# LDAQ-BASE.net
KiCad netlist of a schematic drawn in EAGLE
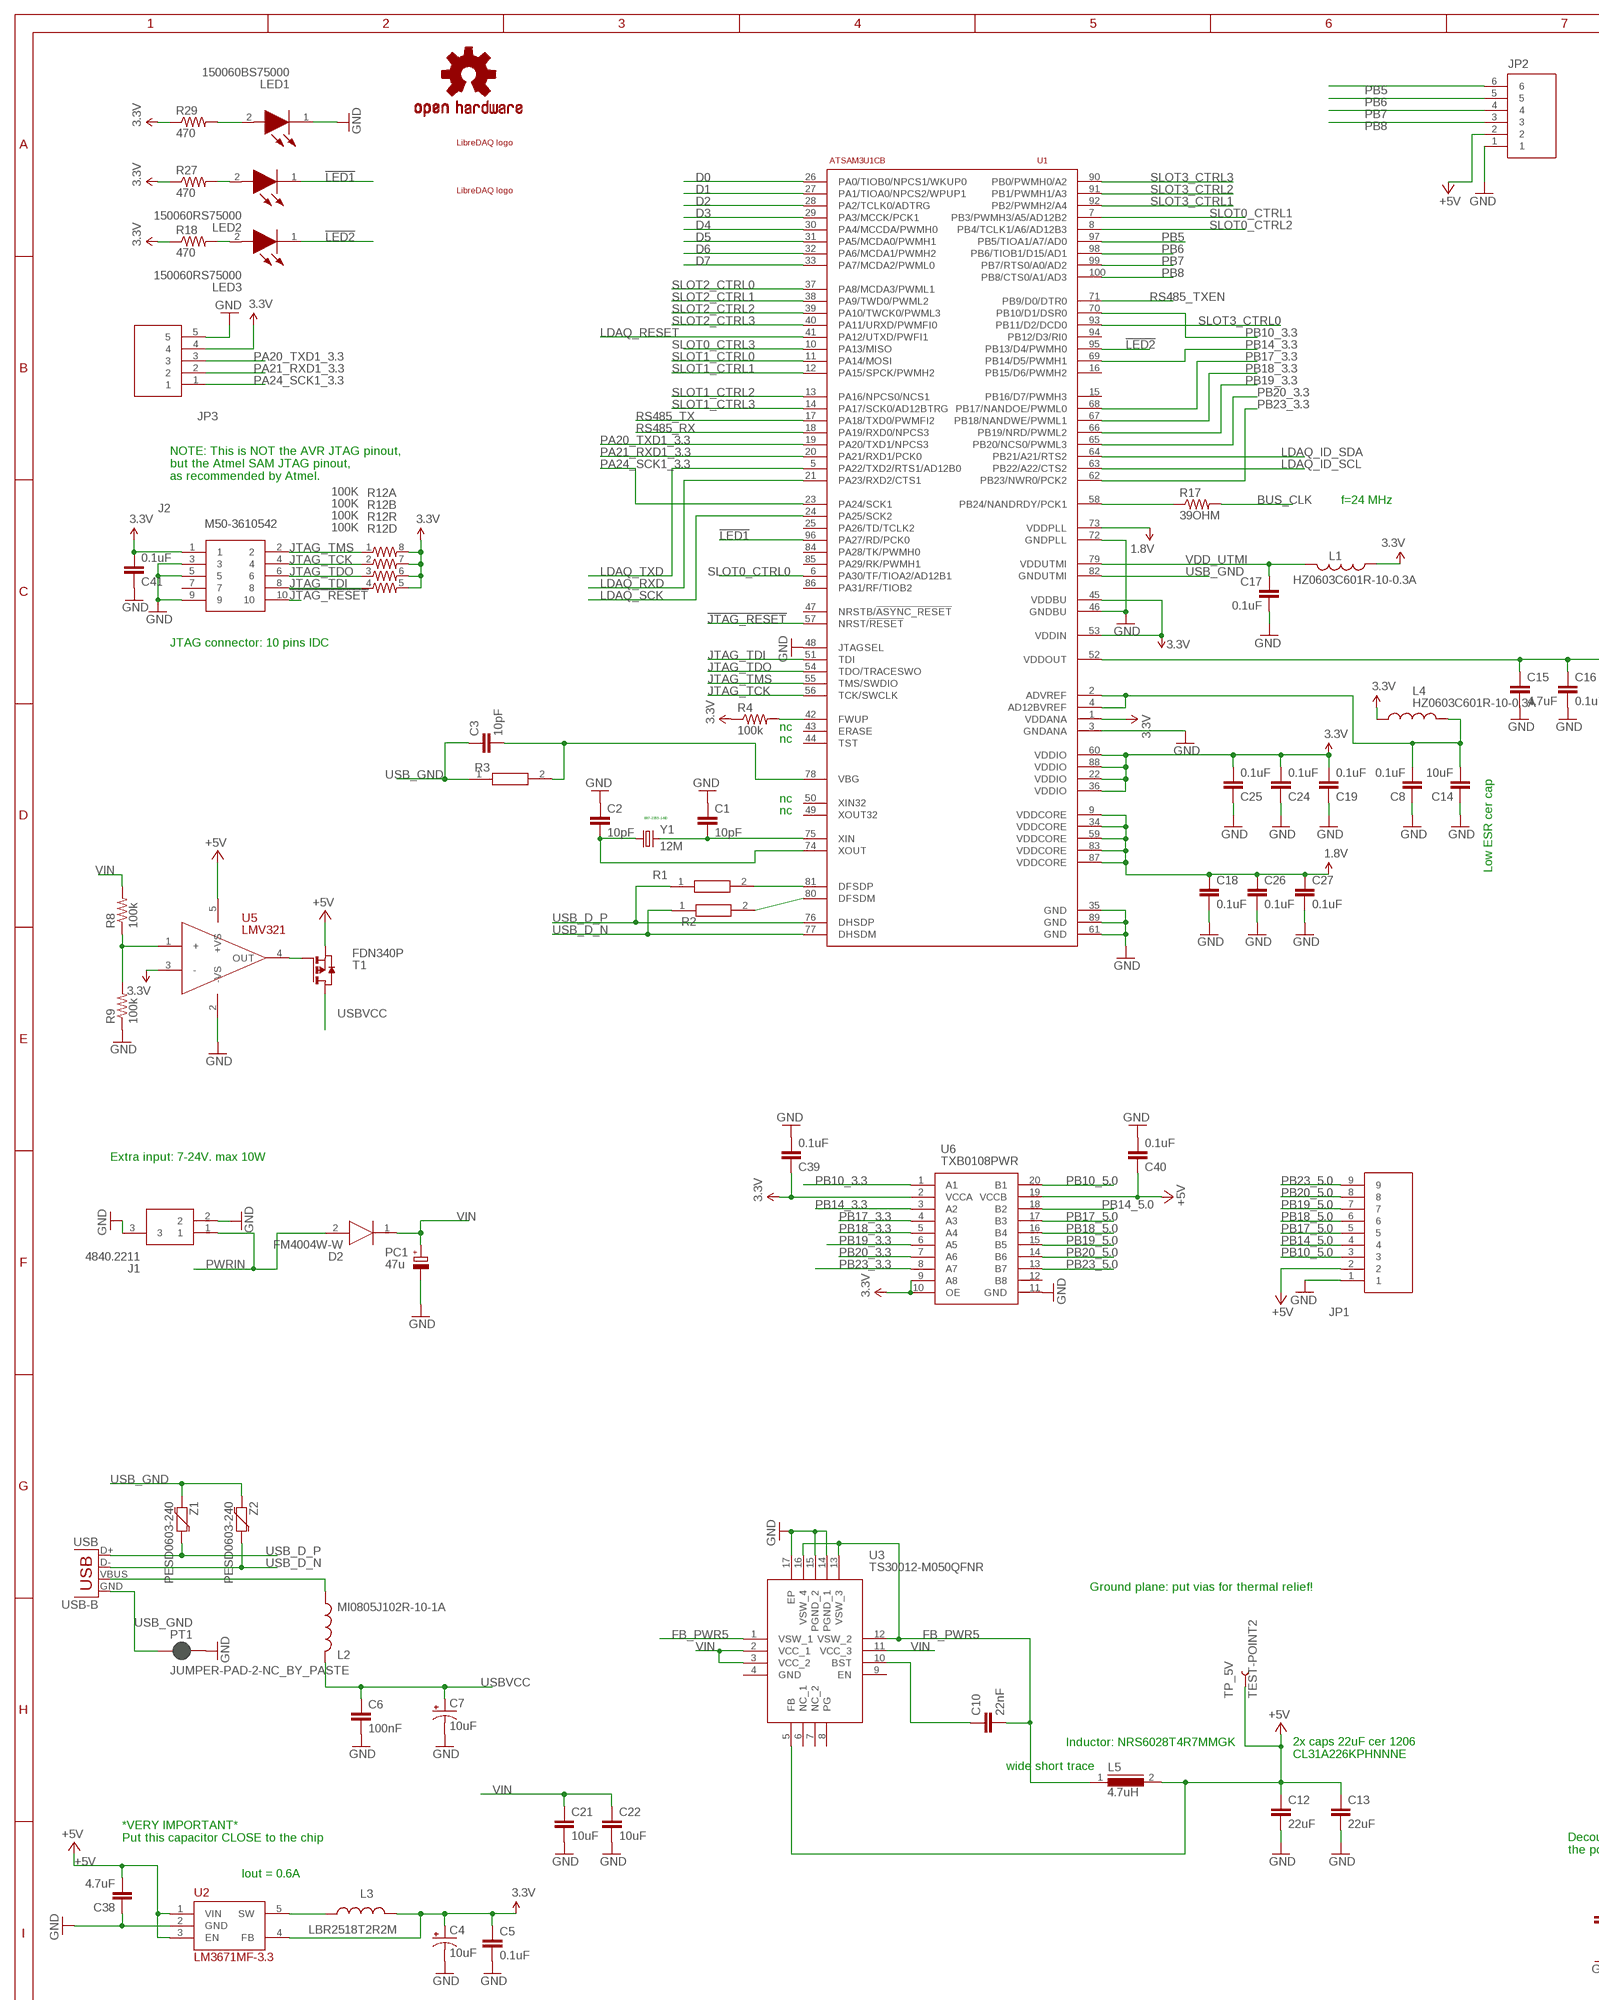
[diagram p0: schematic, sheet 1, part 1 of 2]
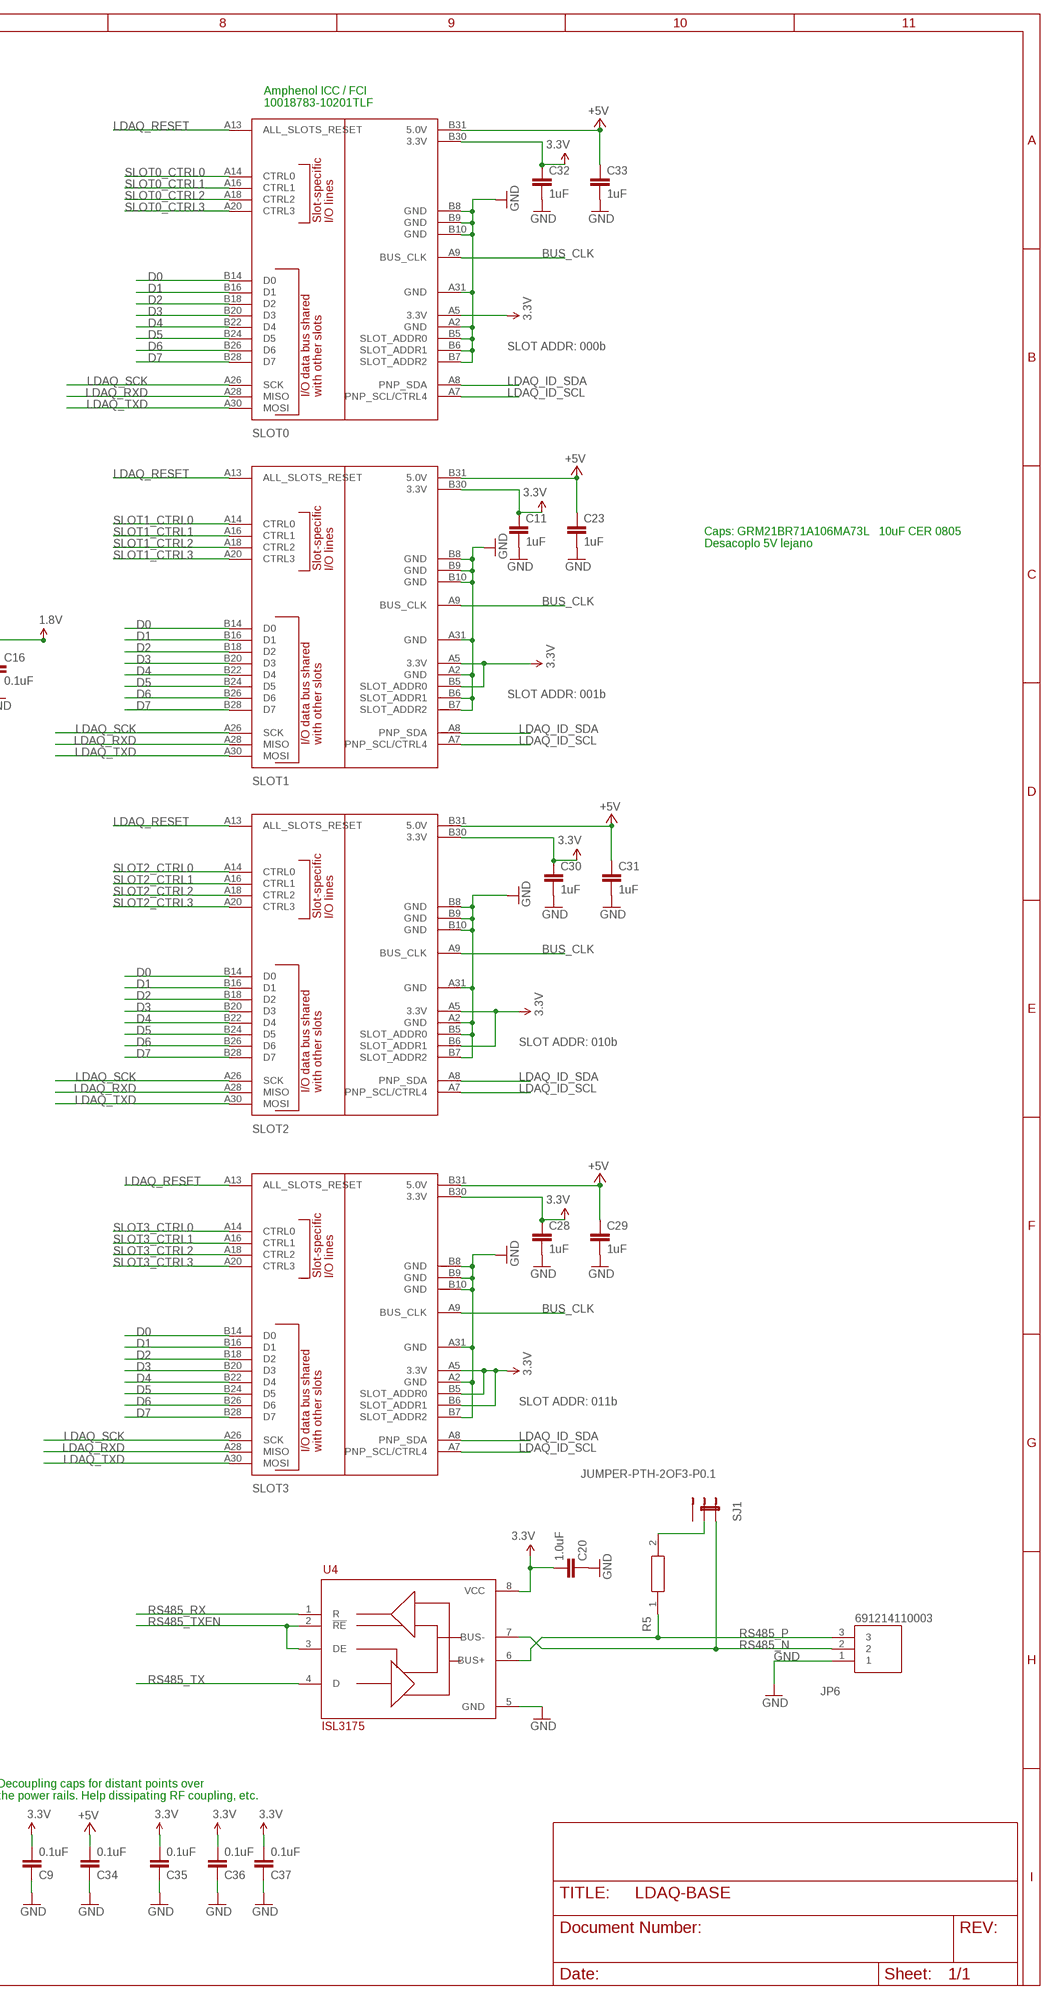
[diagram p1: schematic, sheet 1, part 2 of 2]

(export (version "E")
  (design (tool "Eeschema 10.0.6"))
  (components
    (comp (ref "C1")
      (value "10pF")
      (footprint "eagle-import:0603-CAP")
      (libsource (lib "eagle-import") (part "22PF-50V-5%(0603)"))
    )
    (comp (ref "C2")
      (value "10pF")
      (footprint "eagle-import:0603-CAP")
      (libsource (lib "eagle-import") (part "22PF-50V-5%(0603)"))
    )
    (comp (ref "C3")
      (value "10pF")
      (footprint "eagle-import:0603-CAP")
      (libsource (lib "eagle-import") (part "10PF-50V-5%(0603)"))
    )
    (comp (ref "C4")
      (value "10uF")
      (footprint "eagle-import:EIA3216")
      (libsource (lib "eagle-import") (part "10UF-16V-10%(TANT)"))
    )
    (comp (ref "C5")
      (value "0.1uF")
      (footprint "eagle-import:0603-CAP")
      (libsource (lib "eagle-import") (part "0.1UF-25V(+80/-20%)(0603)"))
    )
    (comp (ref "C6")
      (value "100nF")
      (footprint "eagle-import:0603-CAP")
      (libsource (lib "eagle-import") (part "CAP0603-CAP"))
    )
    (comp (ref "C7")
      (value "10uF")
      (footprint "eagle-import:EIA3216")
      (libsource (lib "eagle-import") (part "CAP_POL1206"))
    )
    (comp (ref "C8")
      (value "0.1uF")
      (footprint "eagle-import:0603-CAP")
      (libsource (lib "eagle-import") (part "0.1UF-25V(+80/-20%)(0603)"))
    )
    (comp (ref "C9")
      (value "0.1uF")
      (footprint "eagle-import:0603-CAP")
      (libsource (lib "eagle-import") (part "0.1UF-25V(+80/-20%)(0603)"))
    )
    (comp (ref "C10")
      (value "22nF")
      (footprint "eagle-import:0603-CAP")
      (libsource (lib "eagle-import") (part "0.1UF-25V(+80/-20%)(0603)"))
    )
    (comp (ref "C11")
      (value "1uF")
      (footprint "eagle-import:0805")
      (libsource (lib "eagle-import") (part "CAP-0805"))
    )
    (comp (ref "C12")
      (value "22uF")
      (footprint "eagle-import:1206")
      (libsource (lib "eagle-import") (part "CAP-1206"))
    )
    (comp (ref "C13")
      (value "22uF")
      (footprint "eagle-import:1206")
      (libsource (lib "eagle-import") (part "CAP-1206"))
    )
    (comp (ref "C14")
      (value "10uF")
      (footprint "eagle-import:0603-CAP")
      (libsource (lib "eagle-import") (part "10UF-6.3V-20%(0603)"))
    )
    (comp (ref "C15")
      (value "4.7uF")
      (footprint "eagle-import:0603-CAP")
      (libsource (lib "eagle-import") (part "4.7UF-6.3V-10%(0603)0603"))
    )
    (comp (ref "C16")
      (value "0.1uF")
      (footprint "eagle-import:0603-CAP")
      (libsource (lib "eagle-import") (part "0.1UF-25V(+80/-20%)(0603)"))
    )
    (comp (ref "C17")
      (value "0.1uF")
      (footprint "eagle-import:0603-CAP")
      (libsource (lib "eagle-import") (part "0.1UF-25V(+80/-20%)(0603)"))
    )
    (comp (ref "C18")
      (value "0.1uF")
      (footprint "eagle-import:0603-CAP")
      (libsource (lib "eagle-import") (part "0.1UF-25V(+80/-20%)(0603)"))
    )
    (comp (ref "C19")
      (value "0.1uF")
      (footprint "eagle-import:0603-CAP")
      (libsource (lib "eagle-import") (part "0.1UF-25V(+80/-20%)(0603)"))
    )
    (comp (ref "C20")
      (value "1.0uF")
      (footprint "eagle-import:0603-CAP")
      (libsource (lib "eagle-import") (part "1.0UF-16V-10%(0603)"))
    )
    (comp (ref "C21")
      (value "10uF")
      (footprint "eagle-import:1206")
      (libsource (lib "eagle-import") (part "CAP-1206"))
    )
    (comp (ref "C22")
      (value "10uF")
      (footprint "eagle-import:1206")
      (libsource (lib "eagle-import") (part "CAP-1206"))
    )
    (comp (ref "C23")
      (value "1uF")
      (footprint "eagle-import:0805")
      (libsource (lib "eagle-import") (part "CAP-0805"))
    )
    (comp (ref "C24")
      (value "0.1uF")
      (footprint "eagle-import:0603-CAP")
      (libsource (lib "eagle-import") (part "0.1UF-25V(+80/-20%)(0603)"))
    )
    (comp (ref "C25")
      (value "0.1uF")
      (footprint "eagle-import:0603-CAP")
      (libsource (lib "eagle-import") (part "0.1UF-25V(+80/-20%)(0603)"))
    )
    (comp (ref "C26")
      (value "0.1uF")
      (footprint "eagle-import:0603-CAP")
      (libsource (lib "eagle-import") (part "0.1UF-25V(+80/-20%)(0603)"))
    )
    (comp (ref "C27")
      (value "0.1uF")
      (footprint "eagle-import:0603-CAP")
      (libsource (lib "eagle-import") (part "0.1UF-25V(+80/-20%)(0603)"))
    )
    (comp (ref "C28")
      (value "1uF")
      (footprint "eagle-import:0805")
      (libsource (lib "eagle-import") (part "CAP-0805"))
    )
    (comp (ref "C29")
      (value "1uF")
      (footprint "eagle-import:0805")
      (libsource (lib "eagle-import") (part "CAP-0805"))
    )
    (comp (ref "C30")
      (value "1uF")
      (footprint "eagle-import:0805")
      (libsource (lib "eagle-import") (part "CAP-0805"))
    )
    (comp (ref "C31")
      (value "1uF")
      (footprint "eagle-import:0805")
      (libsource (lib "eagle-import") (part "CAP-0805"))
    )
    (comp (ref "C32")
      (value "1uF")
      (footprint "eagle-import:0805")
      (libsource (lib "eagle-import") (part "CAP-0805"))
    )
    (comp (ref "C33")
      (value "1uF")
      (footprint "eagle-import:0805")
      (libsource (lib "eagle-import") (part "CAP-0805"))
    )
    (comp (ref "C34")
      (value "0.1uF")
      (footprint "eagle-import:0603-CAP")
      (libsource (lib "eagle-import") (part "0.1UF-25V(+80/-20%)(0603)"))
    )
    (comp (ref "C35")
      (value "0.1uF")
      (footprint "eagle-import:0603-CAP")
      (libsource (lib "eagle-import") (part "0.1UF-25V(+80/-20%)(0603)"))
    )
    (comp (ref "C36")
      (value "0.1uF")
      (footprint "eagle-import:0603-CAP")
      (libsource (lib "eagle-import") (part "0.1UF-25V(+80/-20%)(0603)"))
    )
    (comp (ref "C37")
      (value "0.1uF")
      (footprint "eagle-import:0603-CAP")
      (libsource (lib "eagle-import") (part "0.1UF-25V(+80/-20%)(0603)"))
    )
    (comp (ref "C38")
      (value "4.7uF")
      (footprint "eagle-import:0603-CAP")
      (libsource (lib "eagle-import") (part "0.1UF-25V(+80/-20%)(0603)"))
    )
    (comp (ref "C39")
      (value "0.1uF")
      (footprint "eagle-import:0603-CAP")
      (libsource (lib "eagle-import") (part "0.1UF-25V(+80/-20%)(0603)"))
    )
    (comp (ref "C40")
      (value "0.1uF")
      (footprint "eagle-import:0603-CAP")
      (libsource (lib "eagle-import") (part "0.1UF-25V(+80/-20%)(0603)"))
    )
    (comp (ref "C41")
      (value "0.1uF")
      (footprint "eagle-import:0603-CAP")
      (libsource (lib "eagle-import") (part "0.1UF-25V(+80/-20%)(0603)"))
    )
    (comp (ref "D2")
      (value "FM4004W-W")
      (footprint "eagle-import:DIOM5025X231N")
      (fields (field (name "MOUSER_PART_NUMBER") "583-FM4004W-W"))
      (libsource (lib "eagle-import") (part "FM4004W-W"))
    )
    (comp (ref "J1")
      (value "4840.2211")
      (footprint "eagle-import:48402211")
      (fields (field (name "MOUSER_PART_NUMBER") "693-4840.2211"))
      (libsource (lib "eagle-import") (part "4840.2211"))
    )
    (comp (ref "J2")
      (value "M50-3610542")
      (footprint "eagle-import:M503610542")
      (fields (field (name "MOUSER_PART_NUMBER") "855-M50-3610542"))
      (libsource (lib "eagle-import") (part "M50-3610542"))
    )
    (comp (ref "JP1")
      (value "39357-0009")
      (footprint "eagle-import:393570009")
      (fields (field (name "MOUSER_PART_NUMBER") "538-39357-0009"))
      (libsource (lib "eagle-import") (part "39357-0009"))
    )
    (comp (ref "JP2")
      (value "1984659")
      (footprint "eagle-import:1984659")
      (fields (field (name "MOUSER_PART_NUMBER") "651-1984659"))
      (libsource (lib "eagle-import") (part "1984659"))
    )
    (comp (ref "JP3")
      (value "1984646")
      (footprint "eagle-import:1984646")
      (libsource (lib "eagle-import") (part "1984646"))
    )
    (comp (ref "JP6")
      (value "691214110003")
      (footprint "eagle-import:691214110003")
      (fields (field (name "MOUSER_PART_NUMBER") "710-691214110003"))
      (libsource (lib "eagle-import") (part "691214110003"))
    )
    (comp (ref "L1")
      (value "HZ0603C601R-10-0.3A")
      (footprint "eagle-import:0603")
      (libsource (lib "eagle-import") (part "INDUCTOR0603"))
    )
    (comp (ref "L2")
      (value "MI0805J102R-10-1A")
      (footprint "eagle-import:0805")
      (libsource (lib "eagle-import") (part "INDUCTOR0805"))
    )
    (comp (ref "L3")
      (value "LBR2518T2R2M")
      (footprint "eagle-import:1007")
      (libsource (lib "eagle-import") (part "INDUCTOR1007"))
    )
    (comp (ref "L4")
      (value "HZ0603C601R-10-0.3A")
      (footprint "eagle-import:0603")
      (libsource (lib "eagle-import") (part "INDUCTOR0603"))
    )
    (comp (ref "L5")
      (value "4.7uH")
      (footprint "eagle-import:INDUCTOR_6028")
      (libsource (lib "eagle-import") (part "libredaq-comps_INDUCTOR"))
    )
    (comp (ref "LED1")
      (value "150060BS75000")
      (footprint "eagle-import:LEDC1608X80N")
      (fields (field (name "MOUSER_PART_NUMBER") "710-150060BS75000"))
      (libsource (lib "eagle-import") (part "150060BS75000"))
    )
    (comp (ref "LED2")
      (value "150060RS75000")
      (footprint "eagle-import:LEDC1608X80N")
      (fields (field (name "MOUSER_PART_NUMBER") "710-150060RS75000"))
      (libsource (lib "eagle-import") (part "150060RS75000"))
    )
    (comp (ref "LED3")
      (value "150060RS75000")
      (footprint "eagle-import:LEDC1608X80N")
      (fields (field (name "MOUSER_PART_NUMBER") "710-150060RS75000"))
      (libsource (lib "eagle-import") (part "150060RS75000"))
    )
    (comp (ref "LOGO1")
      (value "OSHW-LOGOL")
      (footprint "eagle-import:OSHW-LOGO-L")
      (libsource (lib "eagle-import") (part "OSHW-LOGOL"))
    )
    (comp (ref "PC1")
      (value "47u")
      (footprint "eagle-import:PANASONIC_D")
      (libsource (lib "eagle-import") (part "CPOL-EUD"))
    )
    (comp (ref "PT1")
      (value "JUMPER-PAD-2-NC_BY_PASTE")
      (footprint "eagle-import:PAD-JUMPER-2-NC_BY_PASTE_YES_SILK")
      (libsource (lib "eagle-import") (part "JUMPER-PAD-2-NC_BY_PASTE"))
    )
    (comp (ref "R1")
      (value "CR1206-FX-39R0ELF")
      (footprint "eagle-import:RESC3216X75N")
      (fields (field (name "MOUSER_PART_NUMBER") "652-CR1206FX-39R0ELF"))
      (libsource (lib "eagle-import") (part "CR1206-FX-39R0ELF"))
    )
    (comp (ref "R2")
      (value "CR1206-FX-39R0ELF")
      (footprint "eagle-import:RESC3216X75N")
      (fields (field (name "MOUSER_PART_NUMBER") "652-CR1206FX-39R0ELF"))
      (libsource (lib "eagle-import") (part "CR1206-FX-39R0ELF"))
    )
    (comp (ref "R3")
      (value "SFR03EZPF6801")
      (footprint "eagle-import:RESC1608X55N")
      (libsource (lib "eagle-import") (part "SFR03EZPF6801"))
    )
    (comp (ref "R4")
      (value "100k")
      (footprint "eagle-import:0603-RES")
      (libsource (lib "eagle-import") (part "100KOHM-1/10W-1%(0603)"))
    )
    (comp (ref "R5")
      (value "CRCW0603120RFKEAC")
      (footprint "eagle-import:RESC1608X55N")
      (fields (field (name "MOUSER_PART_NUMBER") "71-CRCW0603120RFKEAC"))
      (libsource (lib "eagle-import") (part "CRCW0603120RFKEAC"))
    )
    (comp (ref "R8")
      (value "100k")
      (footprint "eagle-import:0603-RES")
      (libsource (lib "eagle-import") (part "100KOHM-1/10W-1%(0603)"))
    )
    (comp (ref "R9")
      (value "100k")
      (footprint "eagle-import:0603-RES")
      (libsource (lib "eagle-import") (part "100KOHM-1/10W-1%(0603)"))
    )
    (comp (ref "R12")
      (value "100K")
      (footprint "eagle-import:0603-ARV")
      (libsource (lib "eagle-import") (part "RESISTOR-ARRAY0603-ARV"))
    )
    (comp (ref "R17")
      (value "39OHM")
      (footprint "eagle-import:0603@1")
      (libsource (lib "eagle-import") (part "33OHM1/10W1%(0603)"))
    )
    (comp (ref "R18")
      (value "470")
      (footprint "eagle-import:0603-RES")
      (libsource (lib "eagle-import") (part "470OHM1/10W1%(0603)"))
    )
    (comp (ref "R27")
      (value "470")
      (footprint "eagle-import:0603-RES")
      (libsource (lib "eagle-import") (part "470OHM1/10W1%(0603)"))
    )
    (comp (ref "R29")
      (value "470")
      (footprint "eagle-import:0603-RES")
      (libsource (lib "eagle-import") (part "470OHM1/10W1%(0603)"))
    )
    (comp (ref "SJ1")
      (value "JUMPER-PTH-2OF3-P0.1")
      (footprint "eagle-import:1X03_LONGPADS")
      (libsource (lib "eagle-import") (part "JUMPER-PTH-2OF3-P0.1"))
    )
    (comp (ref "SLOT0")
      (value "SLOT")
      (footprint "eagle-import:PCI-E_64_PTH_CONN")
      (libsource (lib "eagle-import") (part "LIBREDAQ_DAUGHTER_BOARDPCI-E64-CONN"))
    )
    (comp (ref "SLOT1")
      (value "SLOT")
      (footprint "eagle-import:PCI-E_64_PTH_CONN")
      (libsource (lib "eagle-import") (part "LIBREDAQ_DAUGHTER_BOARDPCI-E64-CONN"))
    )
    (comp (ref "SLOT2")
      (value "SLOT")
      (footprint "eagle-import:PCI-E_64_PTH_CONN")
      (libsource (lib "eagle-import") (part "LIBREDAQ_DAUGHTER_BOARDPCI-E64-CONN"))
    )
    (comp (ref "SLOT3")
      (value "SLOT")
      (footprint "eagle-import:PCI-E_64_PTH_CONN")
      (libsource (lib "eagle-import") (part "LIBREDAQ_DAUGHTER_BOARDPCI-E64-CONN"))
    )
    (comp (ref "T1")
      (value "FDN340P")
      (footprint "eagle-import:SOT-23")
      (libsource (lib "eagle-import") (part "PMOSSOT23"))
    )
    (comp (ref "TP_5V")
      (value "TEST-POINT2")
      (footprint "eagle-import:PAD.02X.02")
      (libsource (lib "eagle-import") (part "TEST-POINT2"))
    )
    (comp (ref "U$1")
      (value "LIBREDAQ_LOGO_MINILOGO_GENERIC")
      (footprint "eagle-import:LIBREDAQ_LOGO")
      (libsource (lib "eagle-import") (part "LIBREDAQ_LOGO_MINILOGO_GENERIC"))
    )
    (comp (ref "U$6")
      (value "LOGO_INDALO")
      (footprint "eagle-import:LIBREDAQ_LOGO_INDALO_ALMERIA")
      (libsource (lib "eagle-import") (part "LOGO_INDALO"))
    )
    (comp (ref "U1")
      (value "ATSAM3U1CB")
      (footprint "eagle-import:TQFP100")
      (libsource (lib "eagle-import") (part "ATSAM3U1CB"))
    )
    (comp (ref "U2")
      (value "LM3671MF-3.3")
      (footprint "eagle-import:TOP23-5")
      (libsource (lib "eagle-import") (part "LM3671MF-3.3"))
    )
    (comp (ref "U3")
      (value "TS30012-M050QFNR")
      (footprint "eagle-import:QFN50P300X300X100-17N")
      (fields (field (name "MOUSER_PART_NUMBER") "947-TS30012-M050QFNR"))
      (libsource (lib "eagle-import") (part "TS30012-M050QFNR"))
    )
    (comp (ref "U4")
      (value "ISL3175")
      (footprint "eagle-import:SOIC8")
      (libsource (lib "eagle-import") (part "ISL3175"))
    )
    (comp (ref "U5")
      (value "LMV321")
      (footprint "eagle-import:SOT353-SC70-5")
      (libsource (lib "eagle-import") (part "LMV321"))
    )
    (comp (ref "U6")
      (value "TXB0108PWR")
      (footprint "eagle-import:SOP65P640X120-20N")
      (fields (field (name "MOUSER_PART_NUMBER") "595-TXB0108PWR"))
      (libsource (lib "eagle-import") (part "TXB0108PWR"))
    )
    (comp (ref "USB")
      (value "USB-B")
      (footprint "eagle-import:USB-B-PTH")
      (libsource (lib "eagle-import") (part "USBPTH"))
    )
    (comp (ref "Y1")
      (value "12M")
      (footprint "eagle-import:CRYSTAL-SMD-5X3")
      (libsource (lib "eagle-import") (part "CRYSTAL5X3"))
    )
    (comp (ref "Z1")
      (value "PESD0603-240")
      (footprint "eagle-import:0603-RES")
      (libsource (lib "eagle-import") (part "VARISTOR-0603"))
    )
    (comp (ref "Z2")
      (value "PESD0603-240")
      (footprint "eagle-import:0603-RES")
      (libsource (lib "eagle-import") (part "VARISTOR-0603"))
    )
  )
  (nets
    (net (code "1") (name "+5V") (class "Default")
      (node (ref "C12") (pin "1") (pinfunction "1_1") (pintype "passive"))
      (node (ref "C13") (pin "1") (pinfunction "1_1") (pintype "passive"))
      (node (ref "C23") (pin "1") (pinfunction "1_1") (pintype "passive"))
      (node (ref "C29") (pin "1") (pinfunction "1_1") (pintype "passive"))
      (node (ref "C31") (pin "1") (pinfunction "1_1") (pintype "passive"))
      (node (ref "C33") (pin "1") (pinfunction "1_1") (pintype "passive"))
      (node (ref "C34") (pin "2") (pinfunction "2_2") (pintype "passive"))
      (node (ref "C38") (pin "2") (pinfunction "2_2") (pintype "passive"))
      (node (ref "C40") (pin "1") (pinfunction "1_1") (pintype "passive"))
      (node (ref "JP1") (pin "2") (pinfunction "2_2") (pintype "bidirectional"))
      (node (ref "JP2") (pin "2") (pinfunction "2_2") (pintype "bidirectional"))
      (node (ref "L5") (pin "2") (pinfunction "2_2") (pintype "passive"))
      (node (ref "SLOT0") (pin "B31") (pinfunction "5.0V_B31") (pintype "bidirectional"))
      (node (ref "SLOT1") (pin "B31") (pinfunction "5.0V_B31") (pintype "bidirectional"))
      (node (ref "SLOT2") (pin "B31") (pinfunction "5.0V_B31") (pintype "bidirectional"))
      (node (ref "SLOT3") (pin "B31") (pinfunction "5.0V_B31") (pintype "bidirectional"))
      (node (ref "T1") (pin "2") (pinfunction "S_2") (pintype "passive"))
      (node (ref "TP_5V") (pin "P$1") (pinfunction "1_P$1") (pintype "bidirectional"))
      (node (ref "U2") (pin "1") (pinfunction "VIN_1") (pintype "bidirectional"))
      (node (ref "U2") (pin "3") (pinfunction "EN_3") (pintype "bidirectional"))
      (node (ref "U3") (pin "5") (pinfunction "FB_5") (pintype "bidirectional"))
      (node (ref "U5") (pin "5") (pinfunction "+VS_5") (pintype "bidirectional"))
      (node (ref "U6") (pin "19") (pinfunction "VCCB_19") (pintype "bidirectional"))
    )
    (net (code "2") (name "/BUS_CLK") (class "Default")
      (node (ref "R17") (pin "2") (pinfunction "2_2") (pintype "passive"))
      (node (ref "SLOT0") (pin "A9") (pinfunction "BUS_CLK_A9") (pintype "bidirectional"))
      (node (ref "SLOT1") (pin "A9") (pinfunction "BUS_CLK_A9") (pintype "bidirectional"))
      (node (ref "SLOT2") (pin "A9") (pinfunction "BUS_CLK_A9") (pintype "bidirectional"))
      (node (ref "SLOT3") (pin "A9") (pinfunction "BUS_CLK_A9") (pintype "bidirectional"))
    )
    (net (code "3") (name "/D0") (class "Default")
      (node (ref "SLOT0") (pin "B14") (pinfunction "D0_B14") (pintype "bidirectional"))
      (node (ref "SLOT1") (pin "B14") (pinfunction "D0_B14") (pintype "bidirectional"))
      (node (ref "SLOT2") (pin "B14") (pinfunction "D0_B14") (pintype "bidirectional"))
      (node (ref "SLOT3") (pin "B14") (pinfunction "D0_B14") (pintype "bidirectional"))
      (node (ref "U1") (pin "26") (pinfunction "PA0/TIOB0/NPCS1/WKUP0_26") (pintype "bidirectional"))
    )
    (net (code "4") (name "/D1") (class "Default")
      (node (ref "SLOT0") (pin "B16") (pinfunction "D1_B16") (pintype "bidirectional"))
      (node (ref "SLOT1") (pin "B16") (pinfunction "D1_B16") (pintype "bidirectional"))
      (node (ref "SLOT2") (pin "B16") (pinfunction "D1_B16") (pintype "bidirectional"))
      (node (ref "SLOT3") (pin "B16") (pinfunction "D1_B16") (pintype "bidirectional"))
      (node (ref "U1") (pin "27") (pinfunction "PA1/TIOA0/NPCS2/WPUP1_27") (pintype "bidirectional"))
    )
    (net (code "5") (name "/D2") (class "Default")
      (node (ref "SLOT0") (pin "B18") (pinfunction "D2_B18") (pintype "bidirectional"))
      (node (ref "SLOT1") (pin "B18") (pinfunction "D2_B18") (pintype "bidirectional"))
      (node (ref "SLOT2") (pin "B18") (pinfunction "D2_B18") (pintype "bidirectional"))
      (node (ref "SLOT3") (pin "B18") (pinfunction "D2_B18") (pintype "bidirectional"))
      (node (ref "U1") (pin "28") (pinfunction "PA2/TCLK0/ADTRG_28") (pintype "bidirectional"))
    )
    (net (code "6") (name "/D3") (class "Default")
      (node (ref "SLOT0") (pin "B20") (pinfunction "D3_B20") (pintype "bidirectional"))
      (node (ref "SLOT1") (pin "B20") (pinfunction "D3_B20") (pintype "bidirectional"))
      (node (ref "SLOT2") (pin "B20") (pinfunction "D3_B20") (pintype "bidirectional"))
      (node (ref "SLOT3") (pin "B20") (pinfunction "D3_B20") (pintype "bidirectional"))
      (node (ref "U1") (pin "29") (pinfunction "PA3/MCCK/PCK1_29") (pintype "bidirectional"))
    )
    (net (code "7") (name "/D4") (class "Default")
      (node (ref "SLOT0") (pin "B22") (pinfunction "D4_B22") (pintype "bidirectional"))
      (node (ref "SLOT1") (pin "B22") (pinfunction "D4_B22") (pintype "bidirectional"))
      (node (ref "SLOT2") (pin "B22") (pinfunction "D4_B22") (pintype "bidirectional"))
      (node (ref "SLOT3") (pin "B22") (pinfunction "D4_B22") (pintype "bidirectional"))
      (node (ref "U1") (pin "30") (pinfunction "PA4/MCCDA/PWMH0_30") (pintype "bidirectional"))
    )
    (net (code "8") (name "/D5") (class "Default")
      (node (ref "SLOT0") (pin "B24") (pinfunction "D5_B24") (pintype "bidirectional"))
      (node (ref "SLOT1") (pin "B24") (pinfunction "D5_B24") (pintype "bidirectional"))
      (node (ref "SLOT2") (pin "B24") (pinfunction "D5_B24") (pintype "bidirectional"))
      (node (ref "SLOT3") (pin "B24") (pinfunction "D5_B24") (pintype "bidirectional"))
      (node (ref "U1") (pin "31") (pinfunction "PA5/MCDA0/PWMH1_31") (pintype "bidirectional"))
    )
    (net (code "9") (name "/D6") (class "Default")
      (node (ref "SLOT0") (pin "B26") (pinfunction "D6_B26") (pintype "bidirectional"))
      (node (ref "SLOT1") (pin "B26") (pinfunction "D6_B26") (pintype "bidirectional"))
      (node (ref "SLOT2") (pin "B26") (pinfunction "D6_B26") (pintype "bidirectional"))
      (node (ref "SLOT3") (pin "B26") (pinfunction "D6_B26") (pintype "bidirectional"))
      (node (ref "U1") (pin "32") (pinfunction "PA6/MCDA1/PWMH2_32") (pintype "bidirectional"))
    )
    (net (code "10") (name "/D7") (class "Default")
      (node (ref "SLOT0") (pin "B28") (pinfunction "D7_B28") (pintype "bidirectional"))
      (node (ref "SLOT1") (pin "B28") (pinfunction "D7_B28") (pintype "bidirectional"))
      (node (ref "SLOT2") (pin "B28") (pinfunction "D7_B28") (pintype "bidirectional"))
      (node (ref "SLOT3") (pin "B28") (pinfunction "D7_B28") (pintype "bidirectional"))
      (node (ref "U1") (pin "33") (pinfunction "PA7/MCDA2/PWML0_33") (pintype "bidirectional"))
    )
    (net (code "11") (name "/FB_PWR5") (class "Default")
      (node (ref "C10") (pin "2") (pinfunction "2_2") (pintype "passive"))
      (node (ref "L5") (pin "1") (pinfunction "1_1") (pintype "passive"))
      (node (ref "U3") (pin "1") (pinfunction "VSW_1_1") (pintype "bidirectional"))
      (node (ref "U3") (pin "12") (pinfunction "VSW_2_12") (pintype "bidirectional"))
      (node (ref "U3") (pin "13") (pinfunction "VSW_3_13") (pintype "bidirectional"))
      (node (ref "U3") (pin "16") (pinfunction "VSW_4_16") (pintype "bidirectional"))
    )
    (net (code "12") (name "/JTAG_TCK") (class "Default")
      (node (ref "J2") (pin "4") (pinfunction "4_4") (pintype "bidirectional"))
      (node (ref "R12") (pin "2") (pinfunction "1_2") (pintype "passive"))
      (node (ref "U1") (pin "56") (pinfunction "TCK/SWCLK_56") (pintype "bidirectional"))
    )
    (net (code "13") (name "/JTAG_TDI") (class "Default")
      (node (ref "J2") (pin "8") (pinfunction "8_8") (pintype "bidirectional"))
      (node (ref "R12") (pin "4") (pinfunction "1_4") (pintype "passive"))
      (node (ref "U1") (pin "51") (pinfunction "TDI_51") (pintype "bidirectional"))
    )
    (net (code "14") (name "/JTAG_TDO") (class "Default")
      (node (ref "J2") (pin "6") (pinfunction "6_6") (pintype "bidirectional"))
      (node (ref "R12") (pin "3") (pinfunction "1_3") (pintype "passive"))
      (node (ref "U1") (pin "54") (pinfunction "TDO/TRACESWO_54") (pintype "bidirectional"))
    )
    (net (code "15") (name "/JTAG_TMS") (class "Default")
      (node (ref "J2") (pin "2") (pinfunction "2_2") (pintype "bidirectional"))
      (node (ref "R12") (pin "1") (pinfunction "1_1") (pintype "passive"))
      (node (ref "U1") (pin "55") (pinfunction "TMS/SWDIO_55") (pintype "bidirectional"))
    )
    (net (code "16") (name "/LDAQ_ID_SCL") (class "Default")
      (node (ref "SLOT0") (pin "A7") (pinfunction "PNP_SCL/CTRL4_A7") (pintype "bidirectional"))
      (node (ref "SLOT1") (pin "A7") (pinfunction "PNP_SCL/CTRL4_A7") (pintype "bidirectional"))
      (node (ref "SLOT2") (pin "A7") (pinfunction "PNP_SCL/CTRL4_A7") (pintype "bidirectional"))
      (node (ref "SLOT3") (pin "A7") (pinfunction "PNP_SCL/CTRL4_A7") (pintype "bidirectional"))
      (node (ref "U1") (pin "63") (pinfunction "PB22/A22/CTS2_63") (pintype "bidirectional"))
    )
    (net (code "17") (name "/LDAQ_ID_SDA") (class "Default")
      (node (ref "SLOT0") (pin "A8") (pinfunction "PNP_SDA_A8") (pintype "bidirectional"))
      (node (ref "SLOT1") (pin "A8") (pinfunction "PNP_SDA_A8") (pintype "bidirectional"))
      (node (ref "SLOT2") (pin "A8") (pinfunction "PNP_SDA_A8") (pintype "bidirectional"))
      (node (ref "SLOT3") (pin "A8") (pinfunction "PNP_SDA_A8") (pintype "bidirectional"))
      (node (ref "U1") (pin "64") (pinfunction "PB21/A21/RTS2_64") (pintype "bidirectional"))
    )
    (net (code "18") (name "/LDAQ_RESET") (class "Default")
      (node (ref "SLOT0") (pin "A13") (pinfunction "ALL_SLOTS_RESET_A13") (pintype "bidirectional"))
      (node (ref "SLOT1") (pin "A13") (pinfunction "ALL_SLOTS_RESET_A13") (pintype "bidirectional"))
      (node (ref "SLOT2") (pin "A13") (pinfunction "ALL_SLOTS_RESET_A13") (pintype "bidirectional"))
      (node (ref "SLOT3") (pin "A13") (pinfunction "ALL_SLOTS_RESET_A13") (pintype "bidirectional"))
      (node (ref "U1") (pin "41") (pinfunction "PA12/UTXD/PWFI1_41") (pintype "bidirectional"))
    )
    (net (code "19") (name "/LDAQ_RXD") (class "Default")
      (node (ref "SLOT0") (pin "A28") (pinfunction "MISO_A28") (pintype "bidirectional"))
      (node (ref "SLOT1") (pin "A28") (pinfunction "MISO_A28") (pintype "bidirectional"))
      (node (ref "SLOT2") (pin "A28") (pinfunction "MISO_A28") (pintype "bidirectional"))
      (node (ref "SLOT3") (pin "A28") (pinfunction "MISO_A28") (pintype "bidirectional"))
      (node (ref "U1") (pin "21") (pinfunction "PA23/RXD2/CTS1_21") (pintype "bidirectional"))
    )
    (net (code "20") (name "/LDAQ_SCK") (class "Default")
      (node (ref "SLOT0") (pin "A26") (pinfunction "SCK_A26") (pintype "bidirectional"))
      (node (ref "SLOT1") (pin "A26") (pinfunction "SCK_A26") (pintype "bidirectional"))
      (node (ref "SLOT2") (pin "A26") (pinfunction "SCK_A26") (pintype "bidirectional"))
      (node (ref "SLOT3") (pin "A26") (pinfunction "SCK_A26") (pintype "bidirectional"))
      (node (ref "U1") (pin "24") (pinfunction "PA25/SCK2_24") (pintype "bidirectional"))
    )
    (net (code "21") (name "/LDAQ_TXD") (class "Default")
      (node (ref "SLOT0") (pin "A30") (pinfunction "MOSI_A30") (pintype "bidirectional"))
      (node (ref "SLOT1") (pin "A30") (pinfunction "MOSI_A30") (pintype "bidirectional"))
      (node (ref "SLOT2") (pin "A30") (pinfunction "MOSI_A30") (pintype "bidirectional"))
      (node (ref "SLOT3") (pin "A30") (pinfunction "MOSI_A30") (pintype "bidirectional"))
      (node (ref "U1") (pin "5") (pinfunction "PA22/TXD2/RTS1/AD12B0_5") (pintype "bidirectional"))
    )
    (net (code "22") (name "/PA20_TXD1_3.3") (class "Default")
      (node (ref "JP3") (pin "3") (pinfunction "3_3") (pintype "bidirectional"))
      (node (ref "U1") (pin "19") (pinfunction "PA20/TXD1/NPCS3_19") (pintype "bidirectional"))
    )
    (net (code "23") (name "/PA21_RXD1_3.3") (class "Default")
      (node (ref "JP3") (pin "2") (pinfunction "2_2") (pintype "bidirectional"))
      (node (ref "U1") (pin "20") (pinfunction "PA21/RXD1/PCK0_20") (pintype "bidirectional"))
    )
    (net (code "24") (name "/PA24_SCK1_3.3") (class "Default")
      (node (ref "JP3") (pin "1") (pinfunction "1_1") (pintype "bidirectional"))
      (node (ref "U1") (pin "23") (pinfunction "PA24/SCK1_23") (pintype "bidirectional"))
    )
    (net (code "25") (name "/PB5") (class "Default")
      (node (ref "JP2") (pin "6") (pinfunction "6_6") (pintype "bidirectional"))
      (node (ref "U1") (pin "97") (pinfunction "PB5/TIOA1/A7/AD0_97") (pintype "bidirectional"))
    )
    (net (code "26") (name "/PB6") (class "Default")
      (node (ref "JP2") (pin "5") (pinfunction "5_5") (pintype "bidirectional"))
      (node (ref "U1") (pin "98") (pinfunction "PB6/TIOB1/D15/AD1_98") (pintype "bidirectional"))
    )
    (net (code "27") (name "/PB7") (class "Default")
      (node (ref "JP2") (pin "4") (pinfunction "4_4") (pintype "bidirectional"))
      (node (ref "U1") (pin "99") (pinfunction "PB7/RTS0/A0/AD2_99") (pintype "bidirectional"))
    )
    (net (code "28") (name "/PB8") (class "Default")
      (node (ref "JP2") (pin "3") (pinfunction "3_3") (pintype "bidirectional"))
      (node (ref "U1") (pin "100") (pinfunction "PB8/CTS0/A1/AD3_100") (pintype "bidirectional"))
    )
    (net (code "29") (name "/PB10_3.3") (class "Default")
      (node (ref "U1") (pin "70") (pinfunction "PB10/D1/DSR0_70") (pintype "bidirectional"))
      (node (ref "U6") (pin "1") (pinfunction "A1_1") (pintype "bidirectional"))
    )
    (net (code "30") (name "/PB10_5.0") (class "Default")
      (node (ref "JP1") (pin "3") (pinfunction "3_3") (pintype "bidirectional"))
      (node (ref "U6") (pin "20") (pinfunction "B1_20") (pintype "bidirectional"))
    )
    (net (code "31") (name "/PB14_3.3") (class "Default")
      (node (ref "U1") (pin "69") (pinfunction "PB14/D5/PWMH1_69") (pintype "bidirectional"))
      (node (ref "U6") (pin "3") (pinfunction "A2_3") (pintype "bidirectional"))
    )
    (net (code "32") (name "/PB14_5.0") (class "Default")
      (node (ref "JP1") (pin "4") (pinfunction "4_4") (pintype "bidirectional"))
      (node (ref "U6") (pin "18") (pinfunction "B2_18") (pintype "bidirectional"))
    )
    (net (code "33") (name "/PB17_3.3") (class "Default")
      (node (ref "U1") (pin "68") (pinfunction "PB17/NANDOE/PWML0_68") (pintype "bidirectional"))
      (node (ref "U6") (pin "4") (pinfunction "A3_4") (pintype "bidirectional"))
    )
    (net (code "34") (name "/PB17_5.0") (class "Default")
      (node (ref "JP1") (pin "5") (pinfunction "5_5") (pintype "bidirectional"))
      (node (ref "U6") (pin "17") (pinfunction "B3_17") (pintype "bidirectional"))
    )
    (net (code "35") (name "/PB18_3.3") (class "Default")
      (node (ref "U1") (pin "67") (pinfunction "PB18/NANDWE/PWML1_67") (pintype "bidirectional"))
      (node (ref "U6") (pin "5") (pinfunction "A4_5") (pintype "bidirectional"))
    )
    (net (code "36") (name "/PB18_5.0") (class "Default")
      (node (ref "JP1") (pin "6") (pinfunction "6_6") (pintype "bidirectional"))
      (node (ref "U6") (pin "16") (pinfunction "B4_16") (pintype "bidirectional"))
    )
    (net (code "37") (name "/PB19_3.3") (class "Default")
      (node (ref "U1") (pin "66") (pinfunction "PB19/NRD/PWML2_66") (pintype "bidirectional"))
      (node (ref "U6") (pin "6") (pinfunction "A5_6") (pintype "bidirectional"))
    )
    (net (code "38") (name "/PB19_5.0") (class "Default")
      (node (ref "JP1") (pin "7") (pinfunction "7_7") (pintype "bidirectional"))
      (node (ref "U6") (pin "15") (pinfunction "B5_15") (pintype "bidirectional"))
    )
    (net (code "39") (name "/PB20_3.3") (class "Default")
      (node (ref "U1") (pin "65") (pinfunction "PB20/NCS0/PWML3_65") (pintype "bidirectional"))
      (node (ref "U6") (pin "7") (pinfunction "A6_7") (pintype "bidirectional"))
    )
    (net (code "40") (name "/PB20_5.0") (class "Default")
      (node (ref "JP1") (pin "8") (pinfunction "8_8") (pintype "bidirectional"))
      (node (ref "U6") (pin "14") (pinfunction "B6_14") (pintype "bidirectional"))
    )
    (net (code "41") (name "/PB23_3.3") (class "Default")
      (node (ref "U1") (pin "62") (pinfunction "PB23/NWR0/PCK2_62") (pintype "bidirectional"))
      (node (ref "U6") (pin "8") (pinfunction "A7_8") (pintype "bidirectional"))
    )
    (net (code "42") (name "/PB23_5.0") (class "Default")
      (node (ref "JP1") (pin "9") (pinfunction "9_9") (pintype "bidirectional"))
      (node (ref "U6") (pin "13") (pinfunction "B7_13") (pintype "bidirectional"))
    )
    (net (code "43") (name "/PWRIN") (class "Default")
      (node (ref "D2") (pin "2") (pinfunction "A_2") (pintype "bidirectional"))
      (node (ref "J1") (pin "1") (pinfunction "1_1") (pintype "bidirectional"))
    )
    (net (code "44") (name "/RS485_N") (class "Default")
      (node (ref "JP6") (pin "2") (pinfunction "2_2") (pintype "bidirectional"))
      (node (ref "SJ1") (pin "1") (pinfunction "1_1") (pintype "passive"))
      (node (ref "U4") (pin "7") (pinfunction "BUS-_7") (pintype "bidirectional"))
    )
    (net (code "45") (name "/RS485_P") (class "Default")
      (node (ref "JP6") (pin "3") (pinfunction "3_3") (pintype "bidirectional"))
      (node (ref "R5") (pin "1") (pinfunction "1_1") (pintype "bidirectional"))
      (node (ref "U4") (pin "6") (pinfunction "BUS+_6") (pintype "bidirectional"))
    )
    (net (code "46") (name "/RS485_RX") (class "Default")
      (node (ref "U1") (pin "18") (pinfunction "PA19/RXD0/NPCS3_18") (pintype "bidirectional"))
      (node (ref "U4") (pin "1") (pinfunction "R_1") (pintype "bidirectional"))
    )
    (net (code "47") (name "/RS485_TX") (class "Default")
      (node (ref "U1") (pin "17") (pinfunction "PA18/TXD0/PWMFI2_17") (pintype "bidirectional"))
      (node (ref "U4") (pin "4") (pinfunction "D_4") (pintype "bidirectional"))
    )
    (net (code "48") (name "/RS485_TXEN") (class "Default")
      (node (ref "U1") (pin "71") (pinfunction "PB9/D0/DTR0_71") (pintype "bidirectional"))
      (node (ref "U4") (pin "2") (pinfunction "~{RE}_2") (pintype "bidirectional"))
      (node (ref "U4") (pin "3") (pinfunction "DE_3") (pintype "bidirectional"))
    )
    (net (code "49") (name "/SLOT0_CTRL0") (class "Default")
      (node (ref "SLOT0") (pin "A14") (pinfunction "CTRL0_A14") (pintype "bidirectional"))
      (node (ref "U1") (pin "6") (pinfunction "PA30/TF/TIOA2/AD12B1_6") (pintype "bidirectional"))
    )
    (net (code "50") (name "/SLOT0_CTRL1") (class "Default")
      (node (ref "SLOT0") (pin "A16") (pinfunction "CTRL1_A16") (pintype "bidirectional"))
      (node (ref "U1") (pin "7") (pinfunction "PB3/PWMH3/A5/AD12B2_7") (pintype "bidirectional"))
    )
    (net (code "51") (name "/SLOT0_CTRL2") (class "Default")
      (node (ref "SLOT0") (pin "A18") (pinfunction "CTRL2_A18") (pintype "bidirectional"))
      (node (ref "U1") (pin "8") (pinfunction "PB4/TCLK1/A6/AD12B3_8") (pintype "bidirectional"))
    )
    (net (code "52") (name "/SLOT0_CTRL3") (class "Default")
      (node (ref "SLOT0") (pin "A20") (pinfunction "CTRL3_A20") (pintype "bidirectional"))
      (node (ref "U1") (pin "10") (pinfunction "PA13/MISO_10") (pintype "bidirectional"))
    )
    (net (code "53") (name "/SLOT1_CTRL0") (class "Default")
      (node (ref "SLOT1") (pin "A14") (pinfunction "CTRL0_A14") (pintype "bidirectional"))
      (node (ref "U1") (pin "11") (pinfunction "PA14/MOSI_11") (pintype "bidirectional"))
    )
    (net (code "54") (name "/SLOT1_CTRL1") (class "Default")
      (node (ref "SLOT1") (pin "A16") (pinfunction "CTRL1_A16") (pintype "bidirectional"))
      (node (ref "U1") (pin "12") (pinfunction "PA15/SPCK/PWMH2_12") (pintype "bidirectional"))
    )
    (net (code "55") (name "/SLOT1_CTRL2") (class "Default")
      (node (ref "SLOT1") (pin "A18") (pinfunction "CTRL2_A18") (pintype "bidirectional"))
      (node (ref "U1") (pin "13") (pinfunction "PA16/NPCS0/NCS1_13") (pintype "bidirectional"))
    )
    (net (code "56") (name "/SLOT1_CTRL3") (class "Default")
      (node (ref "SLOT1") (pin "A20") (pinfunction "CTRL3_A20") (pintype "bidirectional"))
      (node (ref "U1") (pin "14") (pinfunction "PA17/SCK0/AD12BTRG_14") (pintype "bidirectional"))
    )
    (net (code "57") (name "/SLOT2_CTRL0") (class "Default")
      (node (ref "SLOT2") (pin "A14") (pinfunction "CTRL0_A14") (pintype "bidirectional"))
      (node (ref "U1") (pin "37") (pinfunction "PA8/MCDA3/PWML1_37") (pintype "bidirectional"))
    )
    (net (code "58") (name "/SLOT2_CTRL1") (class "Default")
      (node (ref "SLOT2") (pin "A16") (pinfunction "CTRL1_A16") (pintype "bidirectional"))
      (node (ref "U1") (pin "38") (pinfunction "PA9/TWD0/PWML2_38") (pintype "bidirectional"))
    )
    (net (code "59") (name "/SLOT2_CTRL2") (class "Default")
      (node (ref "SLOT2") (pin "A18") (pinfunction "CTRL2_A18") (pintype "bidirectional"))
      (node (ref "U1") (pin "39") (pinfunction "PA10/TWCK0/PWML3_39") (pintype "bidirectional"))
    )
    (net (code "60") (name "/SLOT2_CTRL3") (class "Default")
      (node (ref "SLOT2") (pin "A20") (pinfunction "CTRL3_A20") (pintype "bidirectional"))
      (node (ref "U1") (pin "40") (pinfunction "PA11/URXD/PWMFI0_40") (pintype "bidirectional"))
    )
    (net (code "61") (name "/SLOT3_CTRL0") (class "Default")
      (node (ref "SLOT3") (pin "A14") (pinfunction "CTRL0_A14") (pintype "bidirectional"))
      (node (ref "U1") (pin "93") (pinfunction "PB11/D2/DCD0_93") (pintype "bidirectional"))
    )
    (net (code "62") (name "/SLOT3_CTRL1") (class "Default")
      (node (ref "SLOT3") (pin "A16") (pinfunction "CTRL1_A16") (pintype "bidirectional"))
      (node (ref "U1") (pin "92") (pinfunction "PB2/PWMH2/A4_92") (pintype "bidirectional"))
    )
    (net (code "63") (name "/SLOT3_CTRL2") (class "Default")
      (node (ref "SLOT3") (pin "A18") (pinfunction "CTRL2_A18") (pintype "bidirectional"))
      (node (ref "U1") (pin "91") (pinfunction "PB1/PWMH1/A3_91") (pintype "bidirectional"))
    )
    (net (code "64") (name "/SLOT3_CTRL3") (class "Default")
      (node (ref "SLOT3") (pin "A20") (pinfunction "CTRL3_A20") (pintype "bidirectional"))
      (node (ref "U1") (pin "90") (pinfunction "PB0/PWMH0/A2_90") (pintype "bidirectional"))
    )
    (net (code "65") (name "/USBVCC") (class "Default")
      (node (ref "C6") (pin "1") (pinfunction "1_1") (pintype "passive"))
      (node (ref "C7") (pin "A") (pinfunction "+_A") (pintype "passive"))
      (node (ref "L2") (pin "1") (pinfunction "1_1") (pintype "passive"))
      (node (ref "T1") (pin "1") (pinfunction "D_1") (pintype "passive"))
    )
    (net (code "66") (name "/USB_D_N") (class "Default")
      (node (ref "R2") (pin "1") (pinfunction "1_1") (pintype "bidirectional"))
      (node (ref "U1") (pin "77") (pinfunction "DHSDM_77") (pintype "bidirectional"))
      (node (ref "USB") (pin "D-") (pinfunction "D-_D-") (pintype "bidirectional"))
      (node (ref "Z2") (pin "2") (pinfunction "2_2") (pintype "passive"))
    )
    (net (code "67") (name "/USB_D_P") (class "Default")
      (node (ref "R1") (pin "1") (pinfunction "1_1") (pintype "bidirectional"))
      (node (ref "U1") (pin "76") (pinfunction "DHSDP_76") (pintype "bidirectional"))
      (node (ref "USB") (pin "D+") (pinfunction "D+_D+") (pintype "bidirectional"))
      (node (ref "Z1") (pin "2") (pinfunction "2_2") (pintype "passive"))
    )
    (net (code "68") (name "/USB_GND") (class "Default")
      (node (ref "C3") (pin "1") (pinfunction "1_1") (pintype "passive"))
      (node (ref "PT1") (pin "1") (pinfunction "1_1") (pintype "passive"))
      (node (ref "R3") (pin "1") (pinfunction "1_1") (pintype "bidirectional"))
      (node (ref "U1") (pin "82") (pinfunction "GNDUTMI_82") (pintype "bidirectional"))
      (node (ref "USB") (pin "GND") (pinfunction "GND_GND") (pintype "bidirectional"))
      (node (ref "Z1") (pin "1") (pinfunction "1_1") (pintype "passive"))
      (node (ref "Z2") (pin "1") (pinfunction "1_1") (pintype "passive"))
    )
    (net (code "69") (name "/VDD_UTMI") (class "Default")
      (node (ref "C17") (pin "1") (pinfunction "1_1") (pintype "passive"))
      (node (ref "L1") (pin "1") (pinfunction "1_1") (pintype "passive"))
      (node (ref "U1") (pin "79") (pinfunction "VDDUTMI_79") (pintype "bidirectional"))
    )
    (net (code "70") (name "/VIN") (class "Default")
      (node (ref "C21") (pin "1") (pinfunction "1_1") (pintype "passive"))
      (node (ref "C22") (pin "1") (pinfunction "1_1") (pintype "passive"))
      (node (ref "D2") (pin "1") (pinfunction "K_1") (pintype "bidirectional"))
      (node (ref "PC1") (pin "+") (pinfunction "+_+") (pintype "passive"))
      (node (ref "R8") (pin "2") (pinfunction "2_2") (pintype "passive"))
      (node (ref "U3") (pin "11") (pinfunction "VCC_3_11") (pintype "bidirectional"))
      (node (ref "U3") (pin "2") (pinfunction "VCC_1_2") (pintype "bidirectional"))
      (node (ref "U3") (pin "3") (pinfunction "VCC_2_3") (pintype "bidirectional"))
    )
    (net (code "71") (name "/~{JTAG_RESET}") (class "Default")
      (node (ref "J2") (pin "10") (pinfunction "10_10") (pintype "bidirectional"))
      (node (ref "U1") (pin "57") (pinfunction "NRST/~{RESET}_57") (pintype "bidirectional"))
    )
    (net (code "72") (name "/~{LED1}") (class "Default")
      (node (ref "LED2") (pin "1") (pinfunction "K_1") (pintype "bidirectional"))
      (node (ref "U1") (pin "96") (pinfunction "PA27/RD/PCK0_96") (pintype "bidirectional"))
    )
    (net (code "73") (name "/~{LED2}") (class "Default")
      (node (ref "LED3") (pin "1") (pinfunction "K_1") (pintype "bidirectional"))
      (node (ref "U1") (pin "95") (pinfunction "PB13/D4/PWMH0_95") (pintype "bidirectional"))
    )
    (net (code "74") (name "1.8V") (class "Default")
      (node (ref "C15") (pin "1") (pinfunction "1_1") (pintype "passive"))
      (node (ref "C16") (pin "1") (pinfunction "1_1") (pintype "passive"))
      (node (ref "C18") (pin "1") (pinfunction "1_1") (pintype "passive"))
      (node (ref "C26") (pin "1") (pinfunction "1_1") (pintype "passive"))
      (node (ref "C27") (pin "1") (pinfunction "1_1") (pintype "passive"))
      (node (ref "U1") (pin "34") (pinfunction "VDDCORE_34") (pintype "bidirectional"))
      (node (ref "U1") (pin "52") (pinfunction "VDDOUT_52") (pintype "bidirectional"))
      (node (ref "U1") (pin "59") (pinfunction "VDDCORE_59") (pintype "bidirectional"))
      (node (ref "U1") (pin "73") (pinfunction "VDDPLL_73") (pintype "bidirectional"))
      (node (ref "U1") (pin "83") (pinfunction "VDDCORE_83") (pintype "bidirectional"))
      (node (ref "U1") (pin "87") (pinfunction "VDDCORE_87") (pintype "bidirectional"))
      (node (ref "U1") (pin "9") (pinfunction "VDDCORE_9") (pintype "bidirectional"))
    )
    (net (code "75") (name "3.3V") (class "Default")
      (node (ref "C11") (pin "1") (pinfunction "1_1") (pintype "passive"))
      (node (ref "C19") (pin "2") (pinfunction "2_2") (pintype "passive"))
      (node (ref "C20") (pin "2") (pinfunction "2_2") (pintype "passive"))
      (node (ref "C24") (pin "2") (pinfunction "2_2") (pintype "passive"))
      (node (ref "C25") (pin "2") (pinfunction "2_2") (pintype "passive"))
      (node (ref "C28") (pin "1") (pinfunction "1_1") (pintype "passive"))
      (node (ref "C30") (pin "1") (pinfunction "1_1") (pintype "passive"))
      (node (ref "C32") (pin "1") (pinfunction "1_1") (pintype "passive"))
      (node (ref "C35") (pin "2") (pinfunction "2_2") (pintype "passive"))
      (node (ref "C36") (pin "2") (pinfunction "2_2") (pintype "passive"))
      (node (ref "C37") (pin "2") (pinfunction "2_2") (pintype "passive"))
      (node (ref "C39") (pin "1") (pinfunction "1_1") (pintype "passive"))
      (node (ref "C4") (pin "A") (pinfunction "+_A") (pintype "passive"))
      (node (ref "C41") (pin "2") (pinfunction "2_2") (pintype "passive"))
      (node (ref "C5") (pin "1") (pinfunction "1_1") (pintype "passive"))
      (node (ref "C9") (pin "2") (pinfunction "2_2") (pintype "passive"))
      (node (ref "J2") (pin "1") (pinfunction "1_1") (pintype "bidirectional"))
      (node (ref "JP3") (pin "4") (pinfunction "4_4") (pintype "bidirectional"))
      (node (ref "L1") (pin "2") (pinfunction "2_2") (pintype "passive"))
      (node (ref "L3") (pin "2") (pinfunction "2_2") (pintype "passive"))
      (node (ref "L4") (pin "1") (pinfunction "1_1") (pintype "passive"))
      (node (ref "R12") (pin "5") (pinfunction "2_5") (pintype "passive"))
      (node (ref "R12") (pin "6") (pinfunction "2_6") (pintype "passive"))
      (node (ref "R12") (pin "7") (pinfunction "2_7") (pintype "passive"))
      (node (ref "R12") (pin "8") (pinfunction "2_8") (pintype "passive"))
      (node (ref "R18") (pin "1") (pinfunction "1_1") (pintype "passive"))
      (node (ref "R27") (pin "1") (pinfunction "1_1") (pintype "passive"))
      (node (ref "R29") (pin "1") (pinfunction "1_1") (pintype "passive"))
      (node (ref "R4") (pin "1") (pinfunction "1_1") (pintype "passive"))
      (node (ref "SLOT0") (pin "A5") (pinfunction "3.3V_A5") (pintype "bidirectional"))
      (node (ref "SLOT0") (pin "B30") (pinfunction "3.3V_B30") (pintype "bidirectional"))
      (node (ref "SLOT1") (pin "A5") (pinfunction "3.3V_A5") (pintype "bidirectional"))
      (node (ref "SLOT1") (pin "B30") (pinfunction "3.3V_B30") (pintype "bidirectional"))
      (node (ref "SLOT1") (pin "B5") (pinfunction "SLOT_ADDR0_B5") (pintype "bidirectional"))
      (node (ref "SLOT2") (pin "A5") (pinfunction "3.3V_A5") (pintype "bidirectional"))
      (node (ref "SLOT2") (pin "B30") (pinfunction "3.3V_B30") (pintype "bidirectional"))
      (node (ref "SLOT2") (pin "B6") (pinfunction "SLOT_ADDR1_B6") (pintype "bidirectional"))
      (node (ref "SLOT3") (pin "A5") (pinfunction "3.3V_A5") (pintype "bidirectional"))
      (node (ref "SLOT3") (pin "B30") (pinfunction "3.3V_B30") (pintype "bidirectional"))
      (node (ref "SLOT3") (pin "B5") (pinfunction "SLOT_ADDR0_B5") (pintype "bidirectional"))
      (node (ref "SLOT3") (pin "B6") (pinfunction "SLOT_ADDR1_B6") (pintype "bidirectional"))
      (node (ref "U1") (pin "1") (pinfunction "VDDANA_1") (pintype "bidirectional"))
      (node (ref "U1") (pin "22") (pinfunction "VDDIO_22") (pintype "bidirectional"))
      (node (ref "U1") (pin "36") (pinfunction "VDDIO_36") (pintype "bidirectional"))
      (node (ref "U1") (pin "45") (pinfunction "VDDBU_45") (pintype "bidirectional"))
      (node (ref "U1") (pin "53") (pinfunction "VDDIN_53") (pintype "bidirectional"))
      (node (ref "U1") (pin "60") (pinfunction "VDDIO_60") (pintype "bidirectional"))
      (node (ref "U1") (pin "88") (pinfunction "VDDIO_88") (pintype "bidirectional"))
      (node (ref "U2") (pin "4") (pinfunction "FB_4") (pintype "bidirectional"))
      (node (ref "U4") (pin "8") (pinfunction "VCC_8") (pintype "bidirectional"))
      (node (ref "U5") (pin "3") (pinfunction "-_3") (pintype "bidirectional"))
      (node (ref "U6") (pin "10") (pinfunction "OE_10") (pintype "bidirectional"))
      (node (ref "U6") (pin "2") (pinfunction "VCCA_2") (pintype "bidirectional"))
      (node (ref "U6") (pin "9") (pinfunction "A8_9") (pintype "bidirectional"))
    )
    (net (code "76") (name "GND") (class "Default")
      (node (ref "C1") (pin "1") (pinfunction "1_1") (pintype "passive"))
      (node (ref "C11") (pin "2") (pinfunction "2_2") (pintype "passive"))
      (node (ref "C12") (pin "2") (pinfunction "2_2") (pintype "passive"))
      (node (ref "C13") (pin "2") (pinfunction "2_2") (pintype "passive"))
      (node (ref "C14") (pin "1") (pinfunction "1_1") (pintype "passive"))
      (node (ref "C15") (pin "2") (pinfunction "2_2") (pintype "passive"))
      (node (ref "C16") (pin "2") (pinfunction "2_2") (pintype "passive"))
      (node (ref "C17") (pin "2") (pinfunction "2_2") (pintype "passive"))
      (node (ref "C18") (pin "2") (pinfunction "2_2") (pintype "passive"))
      (node (ref "C19") (pin "1") (pinfunction "1_1") (pintype "passive"))
      (node (ref "C2") (pin "1") (pinfunction "1_1") (pintype "passive"))
      (node (ref "C20") (pin "1") (pinfunction "1_1") (pintype "passive"))
      (node (ref "C21") (pin "2") (pinfunction "2_2") (pintype "passive"))
      (node (ref "C22") (pin "2") (pinfunction "2_2") (pintype "passive"))
      (node (ref "C23") (pin "2") (pinfunction "2_2") (pintype "passive"))
      (node (ref "C24") (pin "1") (pinfunction "1_1") (pintype "passive"))
      (node (ref "C25") (pin "1") (pinfunction "1_1") (pintype "passive"))
      (node (ref "C26") (pin "2") (pinfunction "2_2") (pintype "passive"))
      (node (ref "C27") (pin "2") (pinfunction "2_2") (pintype "passive"))
      (node (ref "C28") (pin "2") (pinfunction "2_2") (pintype "passive"))
      (node (ref "C29") (pin "2") (pinfunction "2_2") (pintype "passive"))
      (node (ref "C30") (pin "2") (pinfunction "2_2") (pintype "passive"))
      (node (ref "C31") (pin "2") (pinfunction "2_2") (pintype "passive"))
      (node (ref "C32") (pin "2") (pinfunction "2_2") (pintype "passive"))
      (node (ref "C33") (pin "2") (pinfunction "2_2") (pintype "passive"))
      (node (ref "C34") (pin "1") (pinfunction "1_1") (pintype "passive"))
      (node (ref "C35") (pin "1") (pinfunction "1_1") (pintype "passive"))
      (node (ref "C36") (pin "1") (pinfunction "1_1") (pintype "passive"))
      (node (ref "C37") (pin "1") (pinfunction "1_1") (pintype "passive"))
      (node (ref "C38") (pin "1") (pinfunction "1_1") (pintype "passive"))
      (node (ref "C39") (pin "2") (pinfunction "2_2") (pintype "passive"))
      (node (ref "C4") (pin "C") (pinfunction "-_C") (pintype "passive"))
      (node (ref "C40") (pin "2") (pinfunction "2_2") (pintype "passive"))
      (node (ref "C41") (pin "1") (pinfunction "1_1") (pintype "passive"))
      (node (ref "C5") (pin "2") (pinfunction "2_2") (pintype "passive"))
      (node (ref "C6") (pin "2") (pinfunction "2_2") (pintype "passive"))
      (node (ref "C7") (pin "C") (pinfunction "-_C") (pintype "passive"))
      (node (ref "C8") (pin "1") (pinfunction "1_1") (pintype "passive"))
      (node (ref "C9") (pin "1") (pinfunction "1_1") (pintype "passive"))
      (node (ref "J1") (pin "2") (pinfunction "2_2") (pintype "bidirectional"))
      (node (ref "J1") (pin "3") (pinfunction "3_3") (pintype "bidirectional"))
      (node (ref "J2") (pin "3") (pinfunction "3_3") (pintype "bidirectional"))
      (node (ref "J2") (pin "5") (pinfunction "5_5") (pintype "bidirectional"))
      (node (ref "J2") (pin "9") (pinfunction "9_9") (pintype "bidirectional"))
      (node (ref "JP1") (pin "1") (pinfunction "1_1") (pintype "bidirectional"))
      (node (ref "JP2") (pin "1") (pinfunction "1_1") (pintype "bidirectional"))
      (node (ref "JP3") (pin "5") (pinfunction "5_5") (pintype "bidirectional"))
      (node (ref "JP6") (pin "1") (pinfunction "1_1") (pintype "bidirectional"))
      (node (ref "LED1") (pin "1") (pinfunction "K_1") (pintype "bidirectional"))
      (node (ref "PC1") (pin "-") (pinfunction "-_-") (pintype "passive"))
      (node (ref "PT1") (pin "2") (pinfunction "2_2") (pintype "passive"))
      (node (ref "R9") (pin "1") (pinfunction "1_1") (pintype "passive"))
      (node (ref "SLOT0") (pin "A2") (pinfunction "GND_A2") (pintype "bidirectional"))
      (node (ref "SLOT0") (pin "A31") (pinfunction "GND_A31") (pintype "bidirectional"))
      (node (ref "SLOT0") (pin "B10") (pinfunction "GND_B10") (pintype "bidirectional"))
      (node (ref "SLOT0") (pin "B5") (pinfunction "SLOT_ADDR0_B5") (pintype "bidirectional"))
      (node (ref "SLOT0") (pin "B6") (pinfunction "SLOT_ADDR1_B6") (pintype "bidirectional"))
      (node (ref "SLOT0") (pin "B7") (pinfunction "SLOT_ADDR2_B7") (pintype "bidirectional"))
      (node (ref "SLOT0") (pin "B8") (pinfunction "GND_B8") (pintype "bidirectional"))
      (node (ref "SLOT0") (pin "B9") (pinfunction "GND_B9") (pintype "bidirectional"))
      (node (ref "SLOT1") (pin "A2") (pinfunction "GND_A2") (pintype "bidirectional"))
      (node (ref "SLOT1") (pin "A31") (pinfunction "GND_A31") (pintype "bidirectional"))
      (node (ref "SLOT1") (pin "B10") (pinfunction "GND_B10") (pintype "bidirectional"))
      (node (ref "SLOT1") (pin "B6") (pinfunction "SLOT_ADDR1_B6") (pintype "bidirectional"))
      (node (ref "SLOT1") (pin "B7") (pinfunction "SLOT_ADDR2_B7") (pintype "bidirectional"))
      (node (ref "SLOT1") (pin "B8") (pinfunction "GND_B8") (pintype "bidirectional"))
      (node (ref "SLOT1") (pin "B9") (pinfunction "GND_B9") (pintype "bidirectional"))
      (node (ref "SLOT2") (pin "A2") (pinfunction "GND_A2") (pintype "bidirectional"))
      (node (ref "SLOT2") (pin "A31") (pinfunction "GND_A31") (pintype "bidirectional"))
      (node (ref "SLOT2") (pin "B10") (pinfunction "GND_B10") (pintype "bidirectional"))
      (node (ref "SLOT2") (pin "B5") (pinfunction "SLOT_ADDR0_B5") (pintype "bidirectional"))
      (node (ref "SLOT2") (pin "B7") (pinfunction "SLOT_ADDR2_B7") (pintype "bidirectional"))
      (node (ref "SLOT2") (pin "B8") (pinfunction "GND_B8") (pintype "bidirectional"))
      (node (ref "SLOT2") (pin "B9") (pinfunction "GND_B9") (pintype "bidirectional"))
      (node (ref "SLOT3") (pin "A2") (pinfunction "GND_A2") (pintype "bidirectional"))
      (node (ref "SLOT3") (pin "A31") (pinfunction "GND_A31") (pintype "bidirectional"))
      (node (ref "SLOT3") (pin "B10") (pinfunction "GND_B10") (pintype "bidirectional"))
      (node (ref "SLOT3") (pin "B7") (pinfunction "SLOT_ADDR2_B7") (pintype "bidirectional"))
      (node (ref "SLOT3") (pin "B8") (pinfunction "GND_B8") (pintype "bidirectional"))
      (node (ref "SLOT3") (pin "B9") (pinfunction "GND_B9") (pintype "bidirectional"))
      (node (ref "U1") (pin "3") (pinfunction "GNDANA_3") (pintype "bidirectional"))
      (node (ref "U1") (pin "35") (pinfunction "GND_35") (pintype "bidirectional"))
      (node (ref "U1") (pin "46") (pinfunction "GNDBU_46") (pintype "bidirectional"))
      (node (ref "U1") (pin "48") (pinfunction "JTAGSEL_48") (pintype "bidirectional"))
      (node (ref "U1") (pin "61") (pinfunction "GND_61") (pintype "bidirectional"))
      (node (ref "U1") (pin "72") (pinfunction "GNDPLL_72") (pintype "bidirectional"))
      (node (ref "U1") (pin "89") (pinfunction "GND_89") (pintype "bidirectional"))
      (node (ref "U2") (pin "2") (pinfunction "GND_2") (pintype "bidirectional"))
      (node (ref "U3") (pin "14") (pinfunction "PGND_1_14") (pintype "bidirectional"))
      (node (ref "U3") (pin "15") (pinfunction "PGND_2_15") (pintype "bidirectional"))
      (node (ref "U3") (pin "17") (pinfunction "EP_17") (pintype "bidirectional"))
      (node (ref "U4") (pin "5") (pinfunction "GND_5") (pintype "bidirectional"))
      (node (ref "U5") (pin "2") (pinfunction "-VS_2") (pintype "bidirectional"))
      (node (ref "U6") (pin "11") (pinfunction "GND_11") (pintype "bidirectional"))
    )
    (net (code "77") (name "Net-(L2-Pad2)") (class "Default")
      (node (ref "L2") (pin "2") (pinfunction "2_2") (pintype "passive"))
      (node (ref "USB") (pin "VBUS") (pinfunction "VBUS_VBUS") (pintype "bidirectional"))
    )
    (net (code "78") (name "Net-(LED1-A)") (class "Default")
      (node (ref "LED1") (pin "2") (pinfunction "A_2") (pintype "bidirectional"))
      (node (ref "R29") (pin "2") (pinfunction "2_2") (pintype "passive"))
    )
    (net (code "79") (name "Net-(LED2-A)") (class "Default")
      (node (ref "LED2") (pin "2") (pinfunction "A_2") (pintype "bidirectional"))
      (node (ref "R27") (pin "2") (pinfunction "2_2") (pintype "passive"))
    )
    (net (code "80") (name "Net-(LED3-A)") (class "Default")
      (node (ref "LED3") (pin "2") (pinfunction "A_2") (pintype "bidirectional"))
      (node (ref "R18") (pin "2") (pinfunction "2_2") (pintype "passive"))
    )
    (net (code "81") (name "Net-(R5-Pad2)") (class "Default")
      (node (ref "R5") (pin "2") (pinfunction "2_2") (pintype "bidirectional"))
      (node (ref "SJ1") (pin "2") (pinfunction "2_2") (pintype "passive"))
    )
    (net (code "82") (name "Net-(T1-G)") (class "Default")
      (node (ref "T1") (pin "3") (pinfunction "G_3") (pintype "passive"))
      (node (ref "U5") (pin "4") (pinfunction "OUT_4") (pintype "bidirectional"))
    )
    (net (code "83") (name "Net-(U1-AD12BVREF)") (class "Default")
      (node (ref "C14") (pin "2") (pinfunction "2_2") (pintype "passive"))
      (node (ref "C8") (pin "2") (pinfunction "2_2") (pintype "passive"))
      (node (ref "L4") (pin "2") (pinfunction "2_2") (pintype "passive"))
      (node (ref "U1") (pin "2") (pinfunction "ADVREF_2") (pintype "bidirectional"))
      (node (ref "U1") (pin "4") (pinfunction "AD12BVREF_4") (pintype "bidirectional"))
    )
    (net (code "84") (name "Net-(U1-DFSDM)") (class "Default")
      (node (ref "R2") (pin "2") (pinfunction "2_2") (pintype "bidirectional"))
      (node (ref "U1") (pin "80") (pinfunction "DFSDM_80") (pintype "bidirectional"))
    )
    (net (code "85") (name "Net-(U1-DFSDP)") (class "Default")
      (node (ref "R1") (pin "2") (pinfunction "2_2") (pintype "bidirectional"))
      (node (ref "U1") (pin "81") (pinfunction "DFSDP_81") (pintype "bidirectional"))
    )
    (net (code "86") (name "Net-(U1-FWUP)") (class "Default")
      (node (ref "R4") (pin "2") (pinfunction "2_2") (pintype "passive"))
      (node (ref "U1") (pin "42") (pinfunction "FWUP_42") (pintype "bidirectional"))
    )
    (net (code "87") (name "Net-(U1-PB24{slash}NANDRDY{slash}PCK1)") (class "Default")
      (node (ref "R17") (pin "1") (pinfunction "1_1") (pintype "passive"))
      (node (ref "U1") (pin "58") (pinfunction "PB24/NANDRDY/PCK1_58") (pintype "bidirectional"))
    )
    (net (code "88") (name "Net-(U1-VBG)") (class "Default")
      (node (ref "C3") (pin "2") (pinfunction "2_2") (pintype "passive"))
      (node (ref "R3") (pin "2") (pinfunction "2_2") (pintype "bidirectional"))
      (node (ref "U1") (pin "78") (pinfunction "VBG_78") (pintype "bidirectional"))
    )
    (net (code "89") (name "Net-(U1-XIN)") (class "Default")
      (node (ref "C1") (pin "2") (pinfunction "2_2") (pintype "passive"))
      (node (ref "U1") (pin "75") (pinfunction "XIN_75") (pintype "bidirectional"))
      (node (ref "Y1") (pin "3") (pinfunction "2_3") (pintype "passive"))
    )
    (net (code "90") (name "Net-(U1-XOUT)") (class "Default")
      (node (ref "C2") (pin "2") (pinfunction "2_2") (pintype "passive"))
      (node (ref "U1") (pin "74") (pinfunction "XOUT_74") (pintype "bidirectional"))
      (node (ref "Y1") (pin "1") (pinfunction "1_1") (pintype "passive"))
    )
    (net (code "91") (name "Net-(U2-SW)") (class "Default")
      (node (ref "L3") (pin "1") (pinfunction "1_1") (pintype "passive"))
      (node (ref "U2") (pin "5") (pinfunction "SW_5") (pintype "bidirectional"))
    )
    (net (code "92") (name "Net-(U3-BST)") (class "Default")
      (node (ref "C10") (pin "1") (pinfunction "1_1") (pintype "passive"))
      (node (ref "U3") (pin "10") (pinfunction "BST_10") (pintype "bidirectional"))
    )
    (net (code "93") (name "Net-(U5-+)") (class "Default")
      (node (ref "R8") (pin "1") (pinfunction "1_1") (pintype "passive"))
      (node (ref "R9") (pin "2") (pinfunction "2_2") (pintype "passive"))
      (node (ref "U5") (pin "1") (pinfunction "+_1") (pintype "bidirectional"))
    )
    (net (code "94") (name "unconnected-(J2-Pad7)") (class "Default")
      (node (ref "J2") (pin "7") (pinfunction "7_7") (pintype "bidirectional"))
    )
    (net (code "95") (name "unconnected-(SJ1-Pad3)") (class "Default")
      (node (ref "SJ1") (pin "3") (pinfunction "3_3") (pintype "passive"))
    )
    (net (code "96") (name "unconnected-(U1-ERASE-Pad43)") (class "Default")
      (node (ref "U1") (pin "43") (pinfunction "ERASE_43") (pintype "bidirectional"))
    )
    (net (code "97") (name "unconnected-(U1-NRSTB{slash}~{ASYNC_RESET}-Pad47)") (class "Default")
      (node (ref "U1") (pin "47") (pinfunction "NRSTB/~{ASYNC_RESET}_47") (pintype "bidirectional"))
    )
    (net (code "98") (name "unconnected-(U1-PA26{slash}TD{slash}TCLK2-Pad25)") (class "Default")
      (node (ref "U1") (pin "25") (pinfunction "PA26/TD/TCLK2_25") (pintype "bidirectional"))
    )
    (net (code "99") (name "unconnected-(U1-PA28{slash}TK{slash}PWMH0-Pad84)") (class "Default")
      (node (ref "U1") (pin "84") (pinfunction "PA28/TK/PWMH0_84") (pintype "bidirectional"))
    )
    (net (code "100") (name "unconnected-(U1-PA29{slash}RK{slash}PWMH1-Pad85)") (class "Default")
      (node (ref "U1") (pin "85") (pinfunction "PA29/RK/PWMH1_85") (pintype "bidirectional"))
    )
    (net (code "101") (name "unconnected-(U1-PA31{slash}RF{slash}TIOB2-Pad86)") (class "Default")
      (node (ref "U1") (pin "86") (pinfunction "PA31/RF/TIOB2_86") (pintype "bidirectional"))
    )
    (net (code "102") (name "unconnected-(U1-PB12{slash}D3{slash}RI0-Pad94)") (class "Default")
      (node (ref "U1") (pin "94") (pinfunction "PB12/D3/RI0_94") (pintype "bidirectional"))
    )
    (net (code "103") (name "unconnected-(U1-PB15{slash}D6{slash}PWMH2-Pad16)") (class "Default")
      (node (ref "U1") (pin "16") (pinfunction "PB15/D6/PWMH2_16") (pintype "bidirectional"))
    )
    (net (code "104") (name "unconnected-(U1-PB16{slash}D7{slash}PWMH3-Pad15)") (class "Default")
      (node (ref "U1") (pin "15") (pinfunction "PB16/D7/PWMH3_15") (pintype "bidirectional"))
    )
    (net (code "105") (name "unconnected-(U1-TST-Pad44)") (class "Default")
      (node (ref "U1") (pin "44") (pinfunction "TST_44") (pintype "bidirectional"))
    )
    (net (code "106") (name "unconnected-(U1-XIN32-Pad50)") (class "Default")
      (node (ref "U1") (pin "50") (pinfunction "XIN32_50") (pintype "bidirectional"))
    )
    (net (code "107") (name "unconnected-(U1-XOUT32-Pad49)") (class "Default")
      (node (ref "U1") (pin "49") (pinfunction "XOUT32_49") (pintype "bidirectional"))
    )
    (net (code "108") (name "unconnected-(U3-EN-Pad9)") (class "Default")
      (node (ref "U3") (pin "9") (pinfunction "EN_9") (pintype "bidirectional"))
    )
    (net (code "109") (name "unconnected-(U3-GND-Pad4)") (class "Default")
      (node (ref "U3") (pin "4") (pinfunction "GND_4") (pintype "bidirectional"))
    )
    (net (code "110") (name "unconnected-(U3-NC_1-Pad6)") (class "Default")
      (node (ref "U3") (pin "6") (pinfunction "NC_1_6") (pintype "bidirectional"))
    )
    (net (code "111") (name "unconnected-(U3-NC_2-Pad7)") (class "Default")
      (node (ref "U3") (pin "7") (pinfunction "NC_2_7") (pintype "bidirectional"))
    )
    (net (code "112") (name "unconnected-(U3-PG-Pad8)") (class "Default")
      (node (ref "U3") (pin "8") (pinfunction "PG_8") (pintype "bidirectional"))
    )
    (net (code "113") (name "unconnected-(U6-B8-Pad12)") (class "Default")
      (node (ref "U6") (pin "12") (pinfunction "B8_12") (pintype "bidirectional"))
    )
  )
)
